# Squibs.net
KiCad netlist of a schematic drawn in Altium Designer
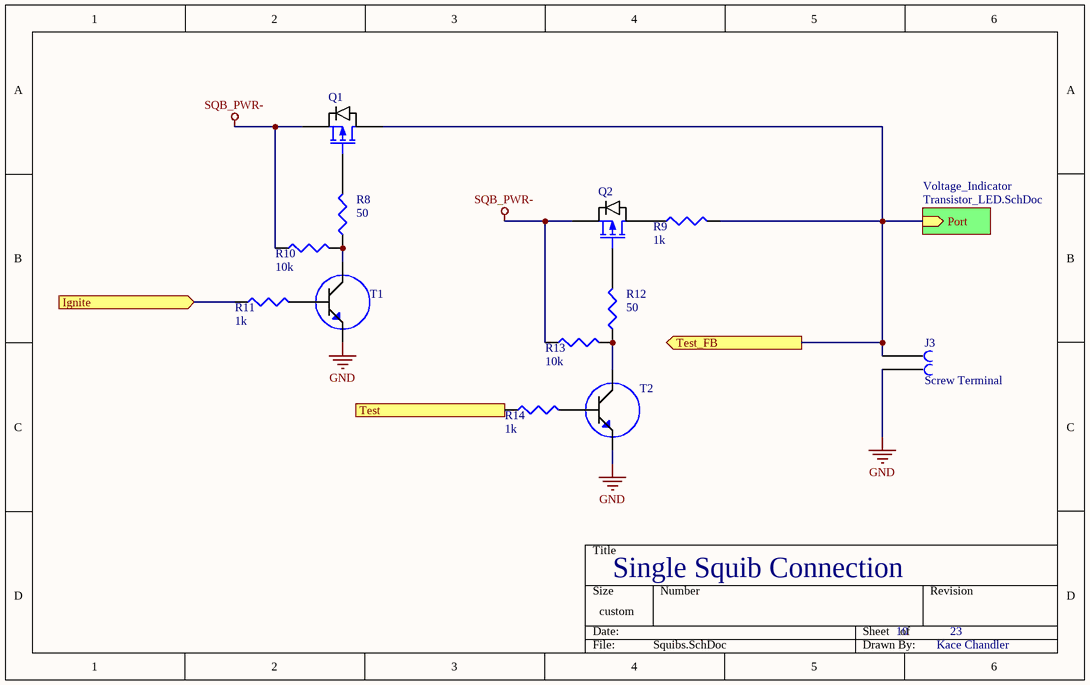
[diagram p0: Squibs.SchDoc]

(export (version "E")
  (design (tool "Eeschema 10.0.6"))
  (components
    (comp (ref "J3")
      (value "Screw Terminal")
      (footprint "Screw Terminal")
      (libsource (lib "AvionicsParts") (part "Screw Terminal"))
    )
    (comp (ref "Q1")
      (value "P-Channel")
      (footprint "P Channel MOSFET")
      (libsource (lib "AvionicsParts") (part "P-Channel"))
    )
    (comp (ref "Q2")
      (value "P-Channel")
      (footprint "P Channel MOSFET")
      (libsource (lib "AvionicsParts") (part "P-Channel"))
    )
    (comp (ref "R8")
      (value "50")
      (description "Resistor")
      (fields (field (name "Comment") "Res3") (field (name "PUBLISHER") "Altium Limited"))
      (libsource (lib "Miscellaneous Devices") (part "Res3"))
    )
    (comp (ref "R9")
      (value "1k")
      (description "Resistor")
      (fields (field (name "Comment") "Res3") (field (name "PUBLISHER") "Altium Limited"))
      (libsource (lib "Miscellaneous Devices") (part "Res3"))
    )
    (comp (ref "R10")
      (value "10k")
      (description "Resistor")
      (fields (field (name "Comment") "Res3") (field (name "PUBLISHER") "Altium Limited"))
      (libsource (lib "Miscellaneous Devices") (part "Res3"))
    )
    (comp (ref "R11")
      (value "1k")
      (description "Resistor")
      (fields (field (name "Comment") "Res3") (field (name "PUBLISHER") "Altium Limited"))
      (libsource (lib "Miscellaneous Devices") (part "Res3"))
    )
    (comp (ref "R12")
      (value "50")
      (description "Resistor")
      (fields (field (name "Comment") "Res3") (field (name "PUBLISHER") "Altium Limited"))
      (libsource (lib "Miscellaneous Devices") (part "Res3"))
    )
    (comp (ref "R13")
      (value "10k")
      (description "Resistor")
      (fields (field (name "Comment") "Res3") (field (name "PUBLISHER") "Altium Limited"))
      (libsource (lib "Miscellaneous Devices") (part "Res3"))
    )
    (comp (ref "R14")
      (value "1k")
      (description "Resistor")
      (fields (field (name "Comment") "Res3") (field (name "PUBLISHER") "Altium Limited"))
      (libsource (lib "Miscellaneous Devices") (part "Res3"))
    )
    (comp (ref "T1")
      (value "MMBT2222ALT1")
      (footprint "BJT")
      (description "Trans NPN 40V 0.6A SOT23")
      (fields (field (name "MF") "ON Semiconductor"))
      (libsource (lib "AvionicsParts") (part "BJT NPN"))
    )
    (comp (ref "T2")
      (value "MMBT2222ALT1")
      (footprint "BJT")
      (description "Trans NPN 40V 0.6A SOT23")
      (fields (field (name "MF") "ON Semiconductor"))
      (libsource (lib "AvionicsParts") (part "BJT NPN"))
    )
  )
  (nets
    (net (code "1") (name "/Ignite") (class "Default")
      (node (ref "R11") (pin "1") (pinfunction "1_1") (pintype "passive"))
    )
    (net (code "2") (name "/Test") (class "Default")
      (node (ref "R14") (pin "1") (pinfunction "1_1") (pintype "passive"))
    )
    (net (code "3") (name "/Test_FB") (class "Default")
      (node (ref "J3") (pin "1") (pinfunction "1_1") (pintype "passive"))
      (node (ref "Q1") (pin "3") (pinfunction "D_3") (pintype "passive"))
      (node (ref "R9") (pin "2") (pinfunction "2_2") (pintype "passive"))
    )
    (net (code "4") (name "GND") (class "Default")
      (node (ref "J3") (pin "2") (pinfunction "2_2") (pintype "passive"))
      (node (ref "T1") (pin "2") (pinfunction "E_2") (pintype "passive"))
      (node (ref "T2") (pin "2") (pinfunction "E_2") (pintype "passive"))
    )
    (net (code "5") (name "Net-(Q1-G)") (class "Default")
      (node (ref "Q1") (pin "1") (pinfunction "G_1") (pintype "passive"))
      (node (ref "R8") (pin "2") (pinfunction "2_2") (pintype "passive"))
    )
    (net (code "6") (name "Net-(Q2-D)") (class "Default")
      (node (ref "Q2") (pin "3") (pinfunction "D_3") (pintype "passive"))
      (node (ref "R9") (pin "1") (pinfunction "1_1") (pintype "passive"))
    )
    (net (code "7") (name "Net-(Q2-G)") (class "Default")
      (node (ref "Q2") (pin "1") (pinfunction "G_1") (pintype "passive"))
      (node (ref "R12") (pin "2") (pinfunction "2_2") (pintype "passive"))
    )
    (net (code "8") (name "Net-(T1-B)") (class "Default")
      (node (ref "R11") (pin "2") (pinfunction "2_2") (pintype "passive"))
      (node (ref "T1") (pin "1") (pinfunction "B_1") (pintype "passive"))
    )
    (net (code "9") (name "Net-(T1-C)") (class "Default")
      (node (ref "R10") (pin "2") (pinfunction "2_2") (pintype "passive"))
      (node (ref "R8") (pin "1") (pinfunction "1_1") (pintype "passive"))
      (node (ref "T1") (pin "3") (pinfunction "C_3") (pintype "passive"))
    )
    (net (code "10") (name "Net-(T2-B)") (class "Default")
      (node (ref "R14") (pin "2") (pinfunction "2_2") (pintype "passive"))
      (node (ref "T2") (pin "1") (pinfunction "B_1") (pintype "passive"))
    )
    (net (code "11") (name "Net-(T2-C)") (class "Default")
      (node (ref "R12") (pin "1") (pinfunction "1_1") (pintype "passive"))
      (node (ref "R13") (pin "2") (pinfunction "2_2") (pintype "passive"))
      (node (ref "T2") (pin "3") (pinfunction "C_3") (pintype "passive"))
    )
    (net (code "12") (name "SQB_PWR-") (class "Default")
      (node (ref "Q1") (pin "2") (pinfunction "S_2") (pintype "passive"))
      (node (ref "Q2") (pin "2") (pinfunction "S_2") (pintype "passive"))
      (node (ref "R10") (pin "1") (pinfunction "1_1") (pintype "passive"))
      (node (ref "R13") (pin "1") (pinfunction "1_1") (pintype "passive"))
    )
  )
)
